# 05_Connector.net
KiCad netlist of a schematic drawn in Altium Designer
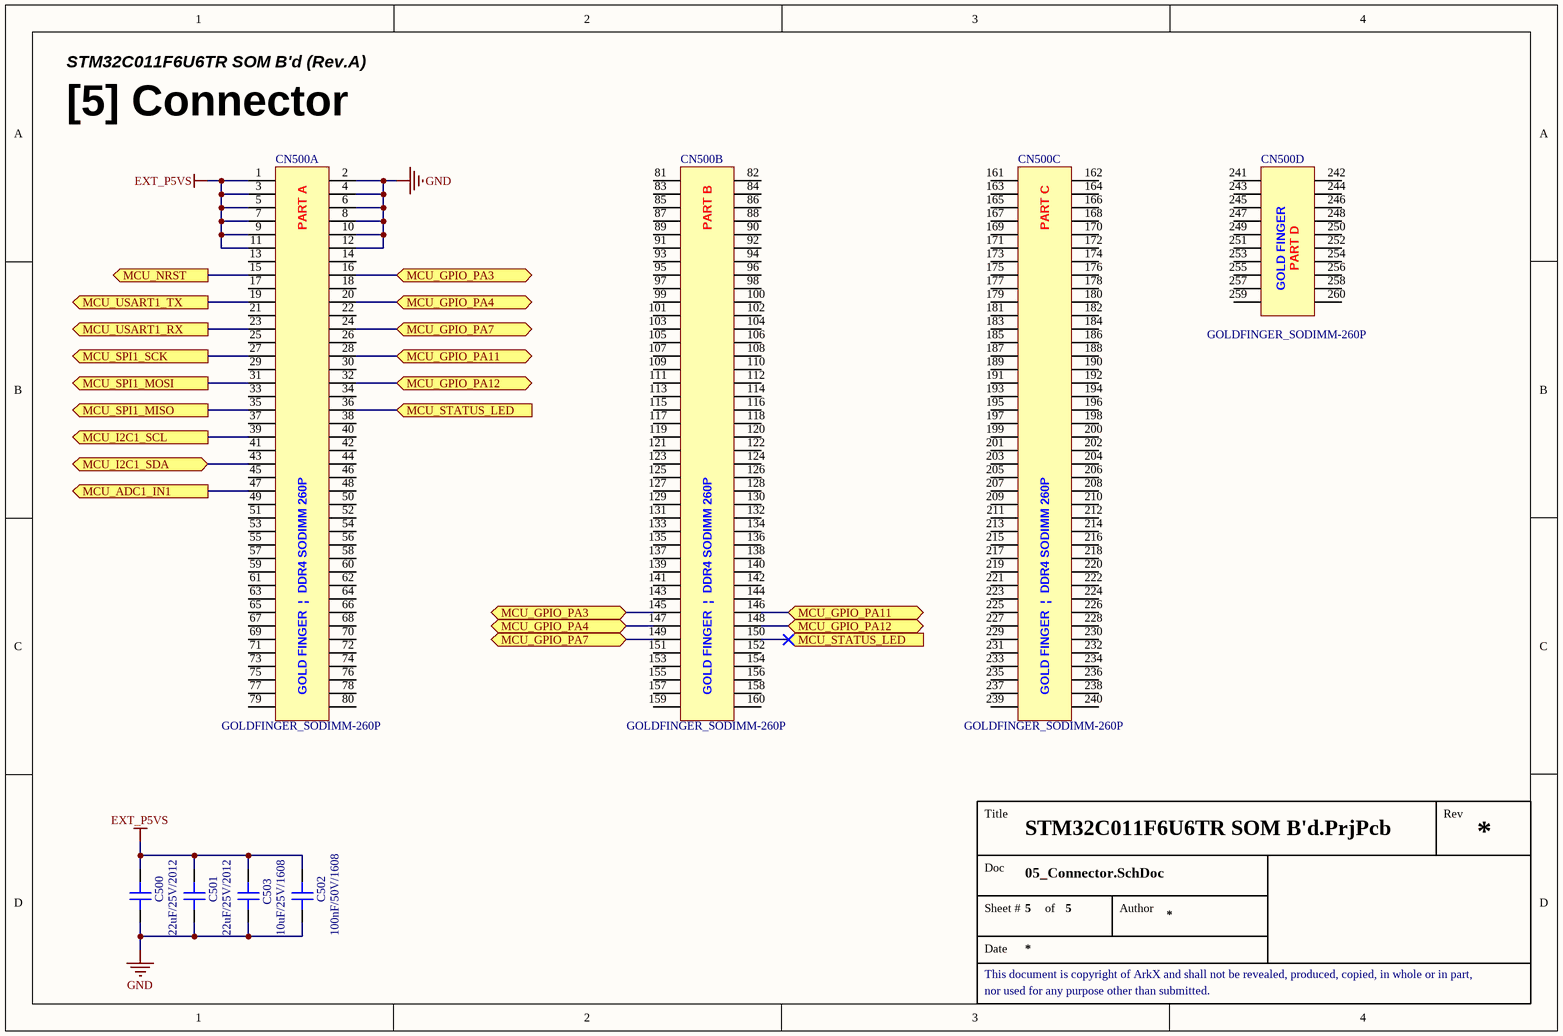
[diagram p0: 05_Connector.SchDoc]

(export (version "E")
  (design (tool "Eeschema 10.0.6"))
  (components
    (comp (ref "C500")
      (value "22uF/25V/2012")
      (footprint "CAP 2012 (0805_INCH)")
      (description "Ceramic CAP_22uF/25V/2012")
      (fields (field (name "LCSC PART #") "C45783"))
      (libsource (lib "Arkx") (part "CAP_22uF/25V/2012"))
    )
    (comp (ref "C501")
      (value "22uF/25V/2012")
      (footprint "CAP 2012 (0805_INCH)")
      (description "Ceramic CAP_22uF/25V/2012")
      (fields (field (name "LCSC PART #") "C45783"))
      (libsource (lib "Arkx") (part "CAP_22uF/25V/2012"))
    )
    (comp (ref "C502")
      (value "100nF/50V/1608")
      (footprint "CAP 1608 (0603_INCH)")
      (description "Ceramic CAP_100nF/50V/1608")
      (fields (field (name "LCSC PART #") "C14663"))
      (libsource (lib "Arkx") (part "CAP_100nF/50V/1608"))
    )
    (comp (ref "C503")
      (value "10uF/25V/1608")
      (footprint "CAP 1608 (0603_INCH)")
      (description "Ceramic CAP_10uF/25V/1608")
      (fields (field (name "LCSC PART #") "C96446"))
      (libsource (lib "Arkx") (part "CAP_10uF/25V/1608"))
    )
    (comp (ref "CN500")
      (value "GOLDFINGER_SODIMM-260P")
      (footprint "CON_DDR4-SODIMM-260P_EDGE-CONNECTOR")
      (description "GOLD-FINGER_DDR4-SODIMM-260P")
      (fields (field (name "MATING PART NUMBER") "2309409-1"))
      (libsource (lib "Arkx") (part "CON_GOLD-FINGER_DDR4-SODIMM-260P"))
    )
  )
  (nets
    (net (code "1") (name "/MCU_ADC1_IN1") (class "Default")
      (node (ref "CN500") (pin "47") (pinfunction "47_47") (pintype "passive"))
    )
    (net (code "2") (name "/MCU_GPIO_PA3") (class "Default")
      (node (ref "CN500") (pin "145") (pinfunction "145_145") (pintype "passive"))
      (node (ref "CN500") (pin "16") (pinfunction "16_16") (pintype "passive"))
    )
    (net (code "3") (name "/MCU_GPIO_PA4") (class "Default")
      (node (ref "CN500") (pin "147") (pinfunction "147_147") (pintype "passive"))
      (node (ref "CN500") (pin "20") (pinfunction "20_20") (pintype "passive"))
    )
    (net (code "4") (name "/MCU_GPIO_PA7") (class "Default")
      (node (ref "CN500") (pin "149") (pinfunction "149_149") (pintype "passive"))
      (node (ref "CN500") (pin "24") (pinfunction "24_24") (pintype "passive"))
    )
    (net (code "5") (name "/MCU_GPIO_PA11") (class "Default")
      (node (ref "CN500") (pin "146") (pinfunction "146_146") (pintype "passive"))
      (node (ref "CN500") (pin "28") (pinfunction "28_28") (pintype "passive"))
    )
    (net (code "6") (name "/MCU_GPIO_PA12") (class "Default")
      (node (ref "CN500") (pin "148") (pinfunction "148_148") (pintype "passive"))
      (node (ref "CN500") (pin "32") (pinfunction "32_32") (pintype "passive"))
    )
    (net (code "7") (name "/MCU_I2C1_SCL") (class "Default")
      (node (ref "CN500") (pin "39") (pinfunction "39_39") (pintype "passive"))
    )
    (net (code "8") (name "/MCU_I2C1_SDA") (class "Default")
      (node (ref "CN500") (pin "43") (pinfunction "43_43") (pintype "passive"))
    )
    (net (code "9") (name "/MCU_NRST") (class "Default")
      (node (ref "CN500") (pin "15") (pinfunction "15_15") (pintype "passive"))
    )
    (net (code "10") (name "/MCU_SPI1_MISO") (class "Default")
      (node (ref "CN500") (pin "35") (pinfunction "35_35") (pintype "passive"))
    )
    (net (code "11") (name "/MCU_SPI1_MOSI") (class "Default")
      (node (ref "CN500") (pin "31") (pinfunction "31_31") (pintype "passive"))
    )
    (net (code "12") (name "/MCU_SPI1_SCK") (class "Default")
      (node (ref "CN500") (pin "27") (pinfunction "27_27") (pintype "passive"))
    )
    (net (code "13") (name "/MCU_STATUS_LED") (class "Default")
      (node (ref "CN500") (pin "150") (pinfunction "150_150") (pintype "passive"))
      (node (ref "CN500") (pin "36") (pinfunction "36_36") (pintype "passive"))
    )
    (net (code "14") (name "/MCU_USART1_RX") (class "Default")
      (node (ref "CN500") (pin "23") (pinfunction "23_23") (pintype "passive"))
    )
    (net (code "15") (name "/MCU_USART1_TX") (class "Default")
      (node (ref "CN500") (pin "19") (pinfunction "19_19") (pintype "passive"))
    )
    (net (code "16") (name "EXT_P5VS") (class "Default")
      (node (ref "C500") (pin "2") (pinfunction "2_2") (pintype "passive"))
      (node (ref "C501") (pin "2") (pinfunction "2_2") (pintype "passive"))
      (node (ref "C502") (pin "2") (pinfunction "2_2") (pintype "passive"))
      (node (ref "C503") (pin "2") (pinfunction "2_2") (pintype "passive"))
      (node (ref "CN500") (pin "1") (pinfunction "1_1") (pintype "passive"))
      (node (ref "CN500") (pin "11") (pinfunction "11_11") (pintype "passive"))
      (node (ref "CN500") (pin "3") (pinfunction "3_3") (pintype "passive"))
      (node (ref "CN500") (pin "5") (pinfunction "5_5") (pintype "passive"))
      (node (ref "CN500") (pin "7") (pinfunction "7_7") (pintype "passive"))
      (node (ref "CN500") (pin "9") (pinfunction "9_9") (pintype "passive"))
    )
    (net (code "17") (name "GND") (class "Default")
      (node (ref "C500") (pin "1") (pinfunction "1_1") (pintype "passive"))
      (node (ref "C501") (pin "1") (pinfunction "1_1") (pintype "passive"))
      (node (ref "C502") (pin "1") (pinfunction "1_1") (pintype "passive"))
      (node (ref "C503") (pin "1") (pinfunction "1_1") (pintype "passive"))
      (node (ref "CN500") (pin "10") (pinfunction "10_10") (pintype "passive"))
      (node (ref "CN500") (pin "12") (pinfunction "12_12") (pintype "passive"))
      (node (ref "CN500") (pin "2") (pinfunction "2_2") (pintype "passive"))
      (node (ref "CN500") (pin "4") (pinfunction "4_4") (pintype "passive"))
      (node (ref "CN500") (pin "6") (pinfunction "6_6") (pintype "passive"))
      (node (ref "CN500") (pin "8") (pinfunction "8_8") (pintype "passive"))
    )
    (net (code "18") (name "unconnected-(CN500-Pad13)") (class "Default")
      (node (ref "CN500") (pin "13") (pinfunction "13_13") (pintype "passive"))
    )
    (net (code "19") (name "unconnected-(CN500-Pad14)") (class "Default")
      (node (ref "CN500") (pin "14") (pinfunction "14_14") (pintype "passive"))
    )
    (net (code "20") (name "unconnected-(CN500-Pad17)") (class "Default")
      (node (ref "CN500") (pin "17") (pinfunction "17_17") (pintype "passive"))
    )
    (net (code "21") (name "unconnected-(CN500-Pad18)") (class "Default")
      (node (ref "CN500") (pin "18") (pinfunction "18_18") (pintype "passive"))
    )
    (net (code "22") (name "unconnected-(CN500-Pad21)") (class "Default")
      (node (ref "CN500") (pin "21") (pinfunction "21_21") (pintype "passive"))
    )
    (net (code "23") (name "unconnected-(CN500-Pad22)") (class "Default")
      (node (ref "CN500") (pin "22") (pinfunction "22_22") (pintype "passive"))
    )
    (net (code "24") (name "unconnected-(CN500-Pad25)") (class "Default")
      (node (ref "CN500") (pin "25") (pinfunction "25_25") (pintype "passive"))
    )
    (net (code "25") (name "unconnected-(CN500-Pad26)") (class "Default")
      (node (ref "CN500") (pin "26") (pinfunction "26_26") (pintype "passive"))
    )
    (net (code "26") (name "unconnected-(CN500-Pad29)") (class "Default")
      (node (ref "CN500") (pin "29") (pinfunction "29_29") (pintype "passive"))
    )
    (net (code "27") (name "unconnected-(CN500-Pad30)") (class "Default")
      (node (ref "CN500") (pin "30") (pinfunction "30_30") (pintype "passive"))
    )
    (net (code "28") (name "unconnected-(CN500-Pad33)") (class "Default")
      (node (ref "CN500") (pin "33") (pinfunction "33_33") (pintype "passive"))
    )
    (net (code "29") (name "unconnected-(CN500-Pad34)") (class "Default")
      (node (ref "CN500") (pin "34") (pinfunction "34_34") (pintype "passive"))
    )
    (net (code "30") (name "unconnected-(CN500-Pad37)") (class "Default")
      (node (ref "CN500") (pin "37") (pinfunction "37_37") (pintype "passive"))
    )
    (net (code "31") (name "unconnected-(CN500-Pad38)") (class "Default")
      (node (ref "CN500") (pin "38") (pinfunction "38_38") (pintype "passive"))
    )
    (net (code "32") (name "unconnected-(CN500-Pad40)") (class "Default")
      (node (ref "CN500") (pin "40") (pinfunction "40_40") (pintype "passive"))
    )
    (net (code "33") (name "unconnected-(CN500-Pad41)") (class "Default")
      (node (ref "CN500") (pin "41") (pinfunction "41_41") (pintype "passive"))
    )
    (net (code "34") (name "unconnected-(CN500-Pad42)") (class "Default")
      (node (ref "CN500") (pin "42") (pinfunction "42_42") (pintype "passive"))
    )
    (net (code "35") (name "unconnected-(CN500-Pad44)") (class "Default")
      (node (ref "CN500") (pin "44") (pinfunction "44_44") (pintype "passive"))
    )
    (net (code "36") (name "unconnected-(CN500-Pad45)") (class "Default")
      (node (ref "CN500") (pin "45") (pinfunction "45_45") (pintype "passive"))
    )
    (net (code "37") (name "unconnected-(CN500-Pad46)") (class "Default")
      (node (ref "CN500") (pin "46") (pinfunction "46_46") (pintype "passive"))
    )
    (net (code "38") (name "unconnected-(CN500-Pad48)") (class "Default")
      (node (ref "CN500") (pin "48") (pinfunction "48_48") (pintype "passive"))
    )
    (net (code "39") (name "unconnected-(CN500-Pad49)") (class "Default")
      (node (ref "CN500") (pin "49") (pinfunction "49_49") (pintype "passive"))
    )
    (net (code "40") (name "unconnected-(CN500-Pad50)") (class "Default")
      (node (ref "CN500") (pin "50") (pinfunction "50_50") (pintype "passive"))
    )
    (net (code "41") (name "unconnected-(CN500-Pad51)") (class "Default")
      (node (ref "CN500") (pin "51") (pinfunction "51_51") (pintype "passive"))
    )
    (net (code "42") (name "unconnected-(CN500-Pad52)") (class "Default")
      (node (ref "CN500") (pin "52") (pinfunction "52_52") (pintype "passive"))
    )
    (net (code "43") (name "unconnected-(CN500-Pad53)") (class "Default")
      (node (ref "CN500") (pin "53") (pinfunction "53_53") (pintype "passive"))
    )
    (net (code "44") (name "unconnected-(CN500-Pad54)") (class "Default")
      (node (ref "CN500") (pin "54") (pinfunction "54_54") (pintype "passive"))
    )
    (net (code "45") (name "unconnected-(CN500-Pad55)") (class "Default")
      (node (ref "CN500") (pin "55") (pinfunction "55_55") (pintype "passive"))
    )
    (net (code "46") (name "unconnected-(CN500-Pad56)") (class "Default")
      (node (ref "CN500") (pin "56") (pinfunction "56_56") (pintype "passive"))
    )
    (net (code "47") (name "unconnected-(CN500-Pad57)") (class "Default")
      (node (ref "CN500") (pin "57") (pinfunction "57_57") (pintype "passive"))
    )
    (net (code "48") (name "unconnected-(CN500-Pad58)") (class "Default")
      (node (ref "CN500") (pin "58") (pinfunction "58_58") (pintype "passive"))
    )
    (net (code "49") (name "unconnected-(CN500-Pad59)") (class "Default")
      (node (ref "CN500") (pin "59") (pinfunction "59_59") (pintype "passive"))
    )
    (net (code "50") (name "unconnected-(CN500-Pad60)") (class "Default")
      (node (ref "CN500") (pin "60") (pinfunction "60_60") (pintype "passive"))
    )
    (net (code "51") (name "unconnected-(CN500-Pad61)") (class "Default")
      (node (ref "CN500") (pin "61") (pinfunction "61_61") (pintype "passive"))
    )
    (net (code "52") (name "unconnected-(CN500-Pad62)") (class "Default")
      (node (ref "CN500") (pin "62") (pinfunction "62_62") (pintype "passive"))
    )
    (net (code "53") (name "unconnected-(CN500-Pad63)") (class "Default")
      (node (ref "CN500") (pin "63") (pinfunction "63_63") (pintype "passive"))
    )
    (net (code "54") (name "unconnected-(CN500-Pad64)") (class "Default")
      (node (ref "CN500") (pin "64") (pinfunction "64_64") (pintype "passive"))
    )
    (net (code "55") (name "unconnected-(CN500-Pad65)") (class "Default")
      (node (ref "CN500") (pin "65") (pinfunction "65_65") (pintype "passive"))
    )
    (net (code "56") (name "unconnected-(CN500-Pad66)") (class "Default")
      (node (ref "CN500") (pin "66") (pinfunction "66_66") (pintype "passive"))
    )
    (net (code "57") (name "unconnected-(CN500-Pad67)") (class "Default")
      (node (ref "CN500") (pin "67") (pinfunction "67_67") (pintype "passive"))
    )
    (net (code "58") (name "unconnected-(CN500-Pad68)") (class "Default")
      (node (ref "CN500") (pin "68") (pinfunction "68_68") (pintype "passive"))
    )
    (net (code "59") (name "unconnected-(CN500-Pad69)") (class "Default")
      (node (ref "CN500") (pin "69") (pinfunction "69_69") (pintype "passive"))
    )
    (net (code "60") (name "unconnected-(CN500-Pad70)") (class "Default")
      (node (ref "CN500") (pin "70") (pinfunction "70_70") (pintype "passive"))
    )
    (net (code "61") (name "unconnected-(CN500-Pad71)") (class "Default")
      (node (ref "CN500") (pin "71") (pinfunction "71_71") (pintype "passive"))
    )
    (net (code "62") (name "unconnected-(CN500-Pad72)") (class "Default")
      (node (ref "CN500") (pin "72") (pinfunction "72_72") (pintype "passive"))
    )
    (net (code "63") (name "unconnected-(CN500-Pad73)") (class "Default")
      (node (ref "CN500") (pin "73") (pinfunction "73_73") (pintype "passive"))
    )
    (net (code "64") (name "unconnected-(CN500-Pad74)") (class "Default")
      (node (ref "CN500") (pin "74") (pinfunction "74_74") (pintype "passive"))
    )
    (net (code "65") (name "unconnected-(CN500-Pad75)") (class "Default")
      (node (ref "CN500") (pin "75") (pinfunction "75_75") (pintype "passive"))
    )
    (net (code "66") (name "unconnected-(CN500-Pad76)") (class "Default")
      (node (ref "CN500") (pin "76") (pinfunction "76_76") (pintype "passive"))
    )
    (net (code "67") (name "unconnected-(CN500-Pad77)") (class "Default")
      (node (ref "CN500") (pin "77") (pinfunction "77_77") (pintype "passive"))
    )
    (net (code "68") (name "unconnected-(CN500-Pad78)") (class "Default")
      (node (ref "CN500") (pin "78") (pinfunction "78_78") (pintype "passive"))
    )
    (net (code "69") (name "unconnected-(CN500-Pad79)") (class "Default")
      (node (ref "CN500") (pin "79") (pinfunction "79_79") (pintype "passive"))
    )
    (net (code "70") (name "unconnected-(CN500-Pad80)") (class "Default")
      (node (ref "CN500") (pin "80") (pinfunction "80_80") (pintype "passive"))
    )
    (net (code "71") (name "unconnected-(CN500-Pad81)") (class "Default")
      (node (ref "CN500") (pin "81") (pinfunction "81_81") (pintype "passive"))
    )
    (net (code "72") (name "unconnected-(CN500-Pad82)") (class "Default")
      (node (ref "CN500") (pin "82") (pinfunction "82_82") (pintype "passive"))
    )
    (net (code "73") (name "unconnected-(CN500-Pad83)") (class "Default")
      (node (ref "CN500") (pin "83") (pinfunction "83_83") (pintype "passive"))
    )
    (net (code "74") (name "unconnected-(CN500-Pad84)") (class "Default")
      (node (ref "CN500") (pin "84") (pinfunction "84_84") (pintype "passive"))
    )
    (net (code "75") (name "unconnected-(CN500-Pad85)") (class "Default")
      (node (ref "CN500") (pin "85") (pinfunction "85_85") (pintype "passive"))
    )
    (net (code "76") (name "unconnected-(CN500-Pad86)") (class "Default")
      (node (ref "CN500") (pin "86") (pinfunction "86_86") (pintype "passive"))
    )
    (net (code "77") (name "unconnected-(CN500-Pad87)") (class "Default")
      (node (ref "CN500") (pin "87") (pinfunction "87_87") (pintype "passive"))
    )
    (net (code "78") (name "unconnected-(CN500-Pad88)") (class "Default")
      (node (ref "CN500") (pin "88") (pinfunction "88_88") (pintype "passive"))
    )
    (net (code "79") (name "unconnected-(CN500-Pad89)") (class "Default")
      (node (ref "CN500") (pin "89") (pinfunction "89_89") (pintype "passive"))
    )
    (net (code "80") (name "unconnected-(CN500-Pad90)") (class "Default")
      (node (ref "CN500") (pin "90") (pinfunction "90_90") (pintype "passive"))
    )
    (net (code "81") (name "unconnected-(CN500-Pad91)") (class "Default")
      (node (ref "CN500") (pin "91") (pinfunction "91_91") (pintype "passive"))
    )
    (net (code "82") (name "unconnected-(CN500-Pad92)") (class "Default")
      (node (ref "CN500") (pin "92") (pinfunction "92_92") (pintype "passive"))
    )
    (net (code "83") (name "unconnected-(CN500-Pad93)") (class "Default")
      (node (ref "CN500") (pin "93") (pinfunction "93_93") (pintype "passive"))
    )
    (net (code "84") (name "unconnected-(CN500-Pad94)") (class "Default")
      (node (ref "CN500") (pin "94") (pinfunction "94_94") (pintype "passive"))
    )
    (net (code "85") (name "unconnected-(CN500-Pad95)") (class "Default")
      (node (ref "CN500") (pin "95") (pinfunction "95_95") (pintype "passive"))
    )
    (net (code "86") (name "unconnected-(CN500-Pad96)") (class "Default")
      (node (ref "CN500") (pin "96") (pinfunction "96_96") (pintype "passive"))
    )
    (net (code "87") (name "unconnected-(CN500-Pad97)") (class "Default")
      (node (ref "CN500") (pin "97") (pinfunction "97_97") (pintype "passive"))
    )
    (net (code "88") (name "unconnected-(CN500-Pad98)") (class "Default")
      (node (ref "CN500") (pin "98") (pinfunction "98_98") (pintype "passive"))
    )
    (net (code "89") (name "unconnected-(CN500-Pad99)") (class "Default")
      (node (ref "CN500") (pin "99") (pinfunction "99_99") (pintype "passive"))
    )
    (net (code "90") (name "unconnected-(CN500-Pad100)") (class "Default")
      (node (ref "CN500") (pin "100") (pinfunction "100_100") (pintype "passive"))
    )
    (net (code "91") (name "unconnected-(CN500-Pad101)") (class "Default")
      (node (ref "CN500") (pin "101") (pinfunction "101_101") (pintype "passive"))
    )
    (net (code "92") (name "unconnected-(CN500-Pad102)") (class "Default")
      (node (ref "CN500") (pin "102") (pinfunction "102_102") (pintype "passive"))
    )
    (net (code "93") (name "unconnected-(CN500-Pad103)") (class "Default")
      (node (ref "CN500") (pin "103") (pinfunction "103_103") (pintype "passive"))
    )
    (net (code "94") (name "unconnected-(CN500-Pad104)") (class "Default")
      (node (ref "CN500") (pin "104") (pinfunction "104_104") (pintype "passive"))
    )
    (net (code "95") (name "unconnected-(CN500-Pad105)") (class "Default")
      (node (ref "CN500") (pin "105") (pinfunction "105_105") (pintype "passive"))
    )
    (net (code "96") (name "unconnected-(CN500-Pad106)") (class "Default")
      (node (ref "CN500") (pin "106") (pinfunction "106_106") (pintype "passive"))
    )
    (net (code "97") (name "unconnected-(CN500-Pad107)") (class "Default")
      (node (ref "CN500") (pin "107") (pinfunction "107_107") (pintype "passive"))
    )
    (net (code "98") (name "unconnected-(CN500-Pad108)") (class "Default")
      (node (ref "CN500") (pin "108") (pinfunction "108_108") (pintype "passive"))
    )
    (net (code "99") (name "unconnected-(CN500-Pad109)") (class "Default")
      (node (ref "CN500") (pin "109") (pinfunction "109_109") (pintype "passive"))
    )
    (net (code "100") (name "unconnected-(CN500-Pad110)") (class "Default")
      (node (ref "CN500") (pin "110") (pinfunction "110_110") (pintype "passive"))
    )
    (net (code "101") (name "unconnected-(CN500-Pad111)") (class "Default")
      (node (ref "CN500") (pin "111") (pinfunction "111_111") (pintype "passive"))
    )
    (net (code "102") (name "unconnected-(CN500-Pad112)") (class "Default")
      (node (ref "CN500") (pin "112") (pinfunction "112_112") (pintype "passive"))
    )
    (net (code "103") (name "unconnected-(CN500-Pad113)") (class "Default")
      (node (ref "CN500") (pin "113") (pinfunction "113_113") (pintype "passive"))
    )
    (net (code "104") (name "unconnected-(CN500-Pad114)") (class "Default")
      (node (ref "CN500") (pin "114") (pinfunction "114_114") (pintype "passive"))
    )
    (net (code "105") (name "unconnected-(CN500-Pad115)") (class "Default")
      (node (ref "CN500") (pin "115") (pinfunction "115_115") (pintype "passive"))
    )
    (net (code "106") (name "unconnected-(CN500-Pad116)") (class "Default")
      (node (ref "CN500") (pin "116") (pinfunction "116_116") (pintype "passive"))
    )
    (net (code "107") (name "unconnected-(CN500-Pad117)") (class "Default")
      (node (ref "CN500") (pin "117") (pinfunction "117_117") (pintype "passive"))
    )
    (net (code "108") (name "unconnected-(CN500-Pad118)") (class "Default")
      (node (ref "CN500") (pin "118") (pinfunction "118_118") (pintype "passive"))
    )
    (net (code "109") (name "unconnected-(CN500-Pad119)") (class "Default")
      (node (ref "CN500") (pin "119") (pinfunction "119_119") (pintype "passive"))
    )
    (net (code "110") (name "unconnected-(CN500-Pad120)") (class "Default")
      (node (ref "CN500") (pin "120") (pinfunction "120_120") (pintype "passive"))
    )
    (net (code "111") (name "unconnected-(CN500-Pad121)") (class "Default")
      (node (ref "CN500") (pin "121") (pinfunction "121_121") (pintype "passive"))
    )
    (net (code "112") (name "unconnected-(CN500-Pad122)") (class "Default")
      (node (ref "CN500") (pin "122") (pinfunction "122_122") (pintype "passive"))
    )
    (net (code "113") (name "unconnected-(CN500-Pad123)") (class "Default")
      (node (ref "CN500") (pin "123") (pinfunction "123_123") (pintype "passive"))
    )
    (net (code "114") (name "unconnected-(CN500-Pad124)") (class "Default")
      (node (ref "CN500") (pin "124") (pinfunction "124_124") (pintype "passive"))
    )
    (net (code "115") (name "unconnected-(CN500-Pad125)") (class "Default")
      (node (ref "CN500") (pin "125") (pinfunction "125_125") (pintype "passive"))
    )
    (net (code "116") (name "unconnected-(CN500-Pad126)") (class "Default")
      (node (ref "CN500") (pin "126") (pinfunction "126_126") (pintype "passive"))
    )
    (net (code "117") (name "unconnected-(CN500-Pad127)") (class "Default")
      (node (ref "CN500") (pin "127") (pinfunction "127_127") (pintype "passive"))
    )
    (net (code "118") (name "unconnected-(CN500-Pad128)") (class "Default")
      (node (ref "CN500") (pin "128") (pinfunction "128_128") (pintype "passive"))
    )
    (net (code "119") (name "unconnected-(CN500-Pad129)") (class "Default")
      (node (ref "CN500") (pin "129") (pinfunction "129_129") (pintype "passive"))
    )
    (net (code "120") (name "unconnected-(CN500-Pad130)") (class "Default")
      (node (ref "CN500") (pin "130") (pinfunction "130_130") (pintype "passive"))
    )
    (net (code "121") (name "unconnected-(CN500-Pad131)") (class "Default")
      (node (ref "CN500") (pin "131") (pinfunction "131_131") (pintype "passive"))
    )
    (net (code "122") (name "unconnected-(CN500-Pad132)") (class "Default")
      (node (ref "CN500") (pin "132") (pinfunction "132_132") (pintype "passive"))
    )
    (net (code "123") (name "unconnected-(CN500-Pad133)") (class "Default")
      (node (ref "CN500") (pin "133") (pinfunction "133_133") (pintype "passive"))
    )
    (net (code "124") (name "unconnected-(CN500-Pad134)") (class "Default")
      (node (ref "CN500") (pin "134") (pinfunction "134_134") (pintype "passive"))
    )
    (net (code "125") (name "unconnected-(CN500-Pad135)") (class "Default")
      (node (ref "CN500") (pin "135") (pinfunction "135_135") (pintype "passive"))
    )
    (net (code "126") (name "unconnected-(CN500-Pad136)") (class "Default")
      (node (ref "CN500") (pin "136") (pinfunction "136_136") (pintype "passive"))
    )
    (net (code "127") (name "unconnected-(CN500-Pad137)") (class "Default")
      (node (ref "CN500") (pin "137") (pinfunction "137_137") (pintype "passive"))
    )
    (net (code "128") (name "unconnected-(CN500-Pad138)") (class "Default")
      (node (ref "CN500") (pin "138") (pinfunction "138_138") (pintype "passive"))
    )
    (net (code "129") (name "unconnected-(CN500-Pad139)") (class "Default")
      (node (ref "CN500") (pin "139") (pinfunction "139_139") (pintype "passive"))
    )
    (net (code "130") (name "unconnected-(CN500-Pad140)") (class "Default")
      (node (ref "CN500") (pin "140") (pinfunction "140_140") (pintype "passive"))
    )
    (net (code "131") (name "unconnected-(CN500-Pad141)") (class "Default")
      (node (ref "CN500") (pin "141") (pinfunction "141_141") (pintype "passive"))
    )
    (net (code "132") (name "unconnected-(CN500-Pad142)") (class "Default")
      (node (ref "CN500") (pin "142") (pinfunction "142_142") (pintype "passive"))
    )
    (net (code "133") (name "unconnected-(CN500-Pad143)") (class "Default")
      (node (ref "CN500") (pin "143") (pinfunction "143_143") (pintype "passive"))
    )
    (net (code "134") (name "unconnected-(CN500-Pad144)") (class "Default")
      (node (ref "CN500") (pin "144") (pinfunction "144_144") (pintype "passive"))
    )
    (net (code "135") (name "unconnected-(CN500-Pad151)") (class "Default")
      (node (ref "CN500") (pin "151") (pinfunction "151_151") (pintype "passive"))
    )
    (net (code "136") (name "unconnected-(CN500-Pad152)") (class "Default")
      (node (ref "CN500") (pin "152") (pinfunction "152_152") (pintype "passive"))
    )
    (net (code "137") (name "unconnected-(CN500-Pad153)") (class "Default")
      (node (ref "CN500") (pin "153") (pinfunction "153_153") (pintype "passive"))
    )
    (net (code "138") (name "unconnected-(CN500-Pad154)") (class "Default")
      (node (ref "CN500") (pin "154") (pinfunction "154_154") (pintype "passive"))
    )
    (net (code "139") (name "unconnected-(CN500-Pad155)") (class "Default")
      (node (ref "CN500") (pin "155") (pinfunction "155_155") (pintype "passive"))
    )
    (net (code "140") (name "unconnected-(CN500-Pad156)") (class "Default")
      (node (ref "CN500") (pin "156") (pinfunction "156_156") (pintype "passive"))
    )
    (net (code "141") (name "unconnected-(CN500-Pad157)") (class "Default")
      (node (ref "CN500") (pin "157") (pinfunction "157_157") (pintype "passive"))
    )
    (net (code "142") (name "unconnected-(CN500-Pad158)") (class "Default")
      (node (ref "CN500") (pin "158") (pinfunction "158_158") (pintype "passive"))
    )
    (net (code "143") (name "unconnected-(CN500-Pad159)") (class "Default")
      (node (ref "CN500") (pin "159") (pinfunction "159_159") (pintype "passive"))
    )
    (net (code "144") (name "unconnected-(CN500-Pad160)") (class "Default")
      (node (ref "CN500") (pin "160") (pinfunction "160_160") (pintype "passive"))
    )
    (net (code "145") (name "unconnected-(CN500-Pad161)") (class "Default")
      (node (ref "CN500") (pin "161") (pinfunction "161_161") (pintype "passive"))
    )
    (net (code "146") (name "unconnected-(CN500-Pad162)") (class "Default")
      (node (ref "CN500") (pin "162") (pinfunction "162_162") (pintype "passive"))
    )
    (net (code "147") (name "unconnected-(CN500-Pad163)") (class "Default")
      (node (ref "CN500") (pin "163") (pinfunction "163_163") (pintype "passive"))
    )
    (net (code "148") (name "unconnected-(CN500-Pad164)") (class "Default")
      (node (ref "CN500") (pin "164") (pinfunction "164_164") (pintype "passive"))
    )
    (net (code "149") (name "unconnected-(CN500-Pad165)") (class "Default")
      (node (ref "CN500") (pin "165") (pinfunction "165_165") (pintype "passive"))
    )
    (net (code "150") (name "unconnected-(CN500-Pad166)") (class "Default")
      (node (ref "CN500") (pin "166") (pinfunction "166_166") (pintype "passive"))
    )
    (net (code "151") (name "unconnected-(CN500-Pad167)") (class "Default")
      (node (ref "CN500") (pin "167") (pinfunction "167_167") (pintype "passive"))
    )
    (net (code "152") (name "unconnected-(CN500-Pad168)") (class "Default")
      (node (ref "CN500") (pin "168") (pinfunction "168_168") (pintype "passive"))
    )
    (net (code "153") (name "unconnected-(CN500-Pad169)") (class "Default")
      (node (ref "CN500") (pin "169") (pinfunction "169_169") (pintype "passive"))
    )
    (net (code "154") (name "unconnected-(CN500-Pad170)") (class "Default")
      (node (ref "CN500") (pin "170") (pinfunction "170_170") (pintype "passive"))
    )
    (net (code "155") (name "unconnected-(CN500-Pad171)") (class "Default")
      (node (ref "CN500") (pin "171") (pinfunction "171_171") (pintype "passive"))
    )
    (net (code "156") (name "unconnected-(CN500-Pad172)") (class "Default")
      (node (ref "CN500") (pin "172") (pinfunction "172_172") (pintype "passive"))
    )
    (net (code "157") (name "unconnected-(CN500-Pad173)") (class "Default")
      (node (ref "CN500") (pin "173") (pinfunction "173_173") (pintype "passive"))
    )
    (net (code "158") (name "unconnected-(CN500-Pad174)") (class "Default")
      (node (ref "CN500") (pin "174") (pinfunction "174_174") (pintype "passive"))
    )
    (net (code "159") (name "unconnected-(CN500-Pad175)") (class "Default")
      (node (ref "CN500") (pin "175") (pinfunction "175_175") (pintype "passive"))
    )
    (net (code "160") (name "unconnected-(CN500-Pad176)") (class "Default")
      (node (ref "CN500") (pin "176") (pinfunction "176_176") (pintype "passive"))
    )
    (net (code "161") (name "unconnected-(CN500-Pad177)") (class "Default")
      (node (ref "CN500") (pin "177") (pinfunction "177_177") (pintype "passive"))
    )
    (net (code "162") (name "unconnected-(CN500-Pad178)") (class "Default")
      (node (ref "CN500") (pin "178") (pinfunction "178_178") (pintype "passive"))
    )
    (net (code "163") (name "unconnected-(CN500-Pad179)") (class "Default")
      (node (ref "CN500") (pin "179") (pinfunction "179_179") (pintype "passive"))
    )
    (net (code "164") (name "unconnected-(CN500-Pad180)") (class "Default")
      (node (ref "CN500") (pin "180") (pinfunction "180_180") (pintype "passive"))
    )
    (net (code "165") (name "unconnected-(CN500-Pad181)") (class "Default")
      (node (ref "CN500") (pin "181") (pinfunction "181_181") (pintype "passive"))
    )
    (net (code "166") (name "unconnected-(CN500-Pad182)") (class "Default")
      (node (ref "CN500") (pin "182") (pinfunction "182_182") (pintype "passive"))
    )
    (net (code "167") (name "unconnected-(CN500-Pad183)") (class "Default")
      (node (ref "CN500") (pin "183") (pinfunction "183_183") (pintype "passive"))
    )
    (net (code "168") (name "unconnected-(CN500-Pad184)") (class "Default")
      (node (ref "CN500") (pin "184") (pinfunction "184_184") (pintype "passive"))
    )
    (net (code "169") (name "unconnected-(CN500-Pad185)") (class "Default")
      (node (ref "CN500") (pin "185") (pinfunction "185_185") (pintype "passive"))
    )
    (net (code "170") (name "unconnected-(CN500-Pad186)") (class "Default")
      (node (ref "CN500") (pin "186") (pinfunction "186_186") (pintype "passive"))
    )
    (net (code "171") (name "unconnected-(CN500-Pad187)") (class "Default")
      (node (ref "CN500") (pin "187") (pinfunction "187_187") (pintype "passive"))
    )
    (net (code "172") (name "unconnected-(CN500-Pad188)") (class "Default")
      (node (ref "CN500") (pin "188") (pinfunction "188_188") (pintype "passive"))
    )
    (net (code "173") (name "unconnected-(CN500-Pad189)") (class "Default")
      (node (ref "CN500") (pin "189") (pinfunction "189_189") (pintype "passive"))
    )
    (net (code "174") (name "unconnected-(CN500-Pad190)") (class "Default")
      (node (ref "CN500") (pin "190") (pinfunction "190_190") (pintype "passive"))
    )
    (net (code "175") (name "unconnected-(CN500-Pad191)") (class "Default")
      (node (ref "CN500") (pin "191") (pinfunction "191_191") (pintype "passive"))
    )
    (net (code "176") (name "unconnected-(CN500-Pad192)") (class "Default")
      (node (ref "CN500") (pin "192") (pinfunction "192_192") (pintype "passive"))
    )
    (net (code "177") (name "unconnected-(CN500-Pad193)") (class "Default")
      (node (ref "CN500") (pin "193") (pinfunction "193_193") (pintype "passive"))
    )
    (net (code "178") (name "unconnected-(CN500-Pad194)") (class "Default")
      (node (ref "CN500") (pin "194") (pinfunction "194_194") (pintype "passive"))
    )
    (net (code "179") (name "unconnected-(CN500-Pad195)") (class "Default")
      (node (ref "CN500") (pin "195") (pinfunction "195_195") (pintype "passive"))
    )
    (net (code "180") (name "unconnected-(CN500-Pad196)") (class "Default")
      (node (ref "CN500") (pin "196") (pinfunction "196_196") (pintype "passive"))
    )
    (net (code "181") (name "unconnected-(CN500-Pad197)") (class "Default")
      (node (ref "CN500") (pin "197") (pinfunction "197_197") (pintype "passive"))
    )
    (net (code "182") (name "unconnected-(CN500-Pad198)") (class "Default")
      (node (ref "CN500") (pin "198") (pinfunction "198_198") (pintype "passive"))
    )
    (net (code "183") (name "unconnected-(CN500-Pad199)") (class "Default")
      (node (ref "CN500") (pin "199") (pinfunction "199_199") (pintype "passive"))
    )
    (net (code "184") (name "unconnected-(CN500-Pad200)") (class "Default")
      (node (ref "CN500") (pin "200") (pinfunction "200_200") (pintype "passive"))
    )
    (net (code "185") (name "unconnected-(CN500-Pad201)") (class "Default")
      (node (ref "CN500") (pin "201") (pinfunction "201_201") (pintype "passive"))
    )
    (net (code "186") (name "unconnected-(CN500-Pad202)") (class "Default")
      (node (ref "CN500") (pin "202") (pinfunction "202_202") (pintype "passive"))
    )
    (net (code "187") (name "unconnected-(CN500-Pad203)") (class "Default")
      (node (ref "CN500") (pin "203") (pinfunction "203_203") (pintype "passive"))
    )
    (net (code "188") (name "unconnected-(CN500-Pad204)") (class "Default")
      (node (ref "CN500") (pin "204") (pinfunction "204_204") (pintype "passive"))
    )
    (net (code "189") (name "unconnected-(CN500-Pad205)") (class "Default")
      (node (ref "CN500") (pin "205") (pinfunction "205_205") (pintype "passive"))
    )
    (net (code "190") (name "unconnected-(CN500-Pad206)") (class "Default")
      (node (ref "CN500") (pin "206") (pinfunction "206_206") (pintype "passive"))
    )
    (net (code "191") (name "unconnected-(CN500-Pad207)") (class "Default")
      (node (ref "CN500") (pin "207") (pinfunction "207_207") (pintype "passive"))
    )
    (net (code "192") (name "unconnected-(CN500-Pad208)") (class "Default")
      (node (ref "CN500") (pin "208") (pinfunction "208_208") (pintype "passive"))
    )
    (net (code "193") (name "unconnected-(CN500-Pad209)") (class "Default")
      (node (ref "CN500") (pin "209") (pinfunction "209_209") (pintype "passive"))
    )
    (net (code "194") (name "unconnected-(CN500-Pad210)") (class "Default")
      (node (ref "CN500") (pin "210") (pinfunction "210_210") (pintype "passive"))
    )
    (net (code "195") (name "unconnected-(CN500-Pad211)") (class "Default")
      (node (ref "CN500") (pin "211") (pinfunction "211_211") (pintype "passive"))
    )
    (net (code "196") (name "unconnected-(CN500-Pad212)") (class "Default")
      (node (ref "CN500") (pin "212") (pinfunction "212_212") (pintype "passive"))
    )
    (net (code "197") (name "unconnected-(CN500-Pad213)") (class "Default")
      (node (ref "CN500") (pin "213") (pinfunction "213_213") (pintype "passive"))
    )
    (net (code "198") (name "unconnected-(CN500-Pad214)") (class "Default")
      (node (ref "CN500") (pin "214") (pinfunction "214_214") (pintype "passive"))
    )
    (net (code "199") (name "unconnected-(CN500-Pad215)") (class "Default")
      (node (ref "CN500") (pin "215") (pinfunction "215_215") (pintype "passive"))
    )
    (net (code "200") (name "unconnected-(CN500-Pad216)") (class "Default")
      (node (ref "CN500") (pin "216") (pinfunction "216_216") (pintype "passive"))
    )
    (net (code "201") (name "unconnected-(CN500-Pad217)") (class "Default")
      (node (ref "CN500") (pin "217") (pinfunction "217_217") (pintype "passive"))
    )
    (net (code "202") (name "unconnected-(CN500-Pad218)") (class "Default")
      (node (ref "CN500") (pin "218") (pinfunction "218_218") (pintype "passive"))
    )
    (net (code "203") (name "unconnected-(CN500-Pad219)") (class "Default")
      (node (ref "CN500") (pin "219") (pinfunction "219_219") (pintype "passive"))
    )
    (net (code "204") (name "unconnected-(CN500-Pad220)") (class "Default")
      (node (ref "CN500") (pin "220") (pinfunction "220_220") (pintype "passive"))
    )
    (net (code "205") (name "unconnected-(CN500-Pad221)") (class "Default")
      (node (ref "CN500") (pin "221") (pinfunction "221_221") (pintype "passive"))
    )
    (net (code "206") (name "unconnected-(CN500-Pad222)") (class "Default")
      (node (ref "CN500") (pin "222") (pinfunction "222_222") (pintype "passive"))
    )
    (net (code "207") (name "unconnected-(CN500-Pad223)") (class "Default")
      (node (ref "CN500") (pin "223") (pinfunction "223_223") (pintype "passive"))
    )
    (net (code "208") (name "unconnected-(CN500-Pad224)") (class "Default")
      (node (ref "CN500") (pin "224") (pinfunction "224_224") (pintype "passive"))
    )
    (net (code "209") (name "unconnected-(CN500-Pad225)") (class "Default")
      (node (ref "CN500") (pin "225") (pinfunction "225_225") (pintype "passive"))
    )
    (net (code "210") (name "unconnected-(CN500-Pad226)") (class "Default")
      (node (ref "CN500") (pin "226") (pinfunction "226_226") (pintype "passive"))
    )
    (net (code "211") (name "unconnected-(CN500-Pad227)") (class "Default")
      (node (ref "CN500") (pin "227") (pinfunction "227_227") (pintype "passive"))
    )
    (net (code "212") (name "unconnected-(CN500-Pad228)") (class "Default")
      (node (ref "CN500") (pin "228") (pinfunction "228_228") (pintype "passive"))
    )
    (net (code "213") (name "unconnected-(CN500-Pad229)") (class "Default")
      (node (ref "CN500") (pin "229") (pinfunction "229_229") (pintype "passive"))
    )
    (net (code "214") (name "unconnected-(CN500-Pad230)") (class "Default")
      (node (ref "CN500") (pin "230") (pinfunction "230_230") (pintype "passive"))
    )
    (net (code "215") (name "unconnected-(CN500-Pad231)") (class "Default")
      (node (ref "CN500") (pin "231") (pinfunction "231_231") (pintype "passive"))
    )
    (net (code "216") (name "unconnected-(CN500-Pad232)") (class "Default")
      (node (ref "CN500") (pin "232") (pinfunction "232_232") (pintype "passive"))
    )
    (net (code "217") (name "unconnected-(CN500-Pad233)") (class "Default")
      (node (ref "CN500") (pin "233") (pinfunction "233_233") (pintype "passive"))
    )
    (net (code "218") (name "unconnected-(CN500-Pad234)") (class "Default")
      (node (ref "CN500") (pin "234") (pinfunction "234_234") (pintype "passive"))
    )
    (net (code "219") (name "unconnected-(CN500-Pad235)") (class "Default")
      (node (ref "CN500") (pin "235") (pinfunction "235_235") (pintype "passive"))
    )
    (net (code "220") (name "unconnected-(CN500-Pad236)") (class "Default")
      (node (ref "CN500") (pin "236") (pinfunction "236_236") (pintype "passive"))
    )
    (net (code "221") (name "unconnected-(CN500-Pad237)") (class "Default")
      (node (ref "CN500") (pin "237") (pinfunction "237_237") (pintype "passive"))
    )
    (net (code "222") (name "unconnected-(CN500-Pad238)") (class "Default")
      (node (ref "CN500") (pin "238") (pinfunction "238_238") (pintype "passive"))
    )
    (net (code "223") (name "unconnected-(CN500-Pad239)") (class "Default")
      (node (ref "CN500") (pin "239") (pinfunction "239_239") (pintype "passive"))
    )
    (net (code "224") (name "unconnected-(CN500-Pad240)") (class "Default")
      (node (ref "CN500") (pin "240") (pinfunction "240_240") (pintype "passive"))
    )
    (net (code "225") (name "unconnected-(CN500-Pad241)") (class "Default")
      (node (ref "CN500") (pin "241") (pinfunction "241_241") (pintype "passive"))
    )
    (net (code "226") (name "unconnected-(CN500-Pad242)") (class "Default")
      (node (ref "CN500") (pin "242") (pinfunction "242_242") (pintype "passive"))
    )
    (net (code "227") (name "unconnected-(CN500-Pad243)") (class "Default")
      (node (ref "CN500") (pin "243") (pinfunction "243_243") (pintype "passive"))
    )
    (net (code "228") (name "unconnected-(CN500-Pad244)") (class "Default")
      (node (ref "CN500") (pin "244") (pinfunction "244_244") (pintype "passive"))
    )
    (net (code "229") (name "unconnected-(CN500-Pad245)") (class "Default")
      (node (ref "CN500") (pin "245") (pinfunction "245_245") (pintype "passive"))
    )
    (net (code "230") (name "unconnected-(CN500-Pad246)") (class "Default")
      (node (ref "CN500") (pin "246") (pinfunction "246_246") (pintype "passive"))
    )
    (net (code "231") (name "unconnected-(CN500-Pad247)") (class "Default")
      (node (ref "CN500") (pin "247") (pinfunction "247_247") (pintype "passive"))
    )
    (net (code "232") (name "unconnected-(CN500-Pad248)") (class "Default")
      (node (ref "CN500") (pin "248") (pinfunction "248_248") (pintype "passive"))
    )
    (net (code "233") (name "unconnected-(CN500-Pad249)") (class "Default")
      (node (ref "CN500") (pin "249") (pinfunction "249_249") (pintype "passive"))
    )
    (net (code "234") (name "unconnected-(CN500-Pad250)") (class "Default")
      (node (ref "CN500") (pin "250") (pinfunction "250_250") (pintype "passive"))
    )
    (net (code "235") (name "unconnected-(CN500-Pad251)") (class "Default")
      (node (ref "CN500") (pin "251") (pinfunction "251_251") (pintype "passive"))
    )
    (net (code "236") (name "unconnected-(CN500-Pad252)") (class "Default")
      (node (ref "CN500") (pin "252") (pinfunction "252_252") (pintype "passive"))
    )
    (net (code "237") (name "unconnected-(CN500-Pad253)") (class "Default")
      (node (ref "CN500") (pin "253") (pinfunction "253_253") (pintype "passive"))
    )
    (net (code "238") (name "unconnected-(CN500-Pad254)") (class "Default")
      (node (ref "CN500") (pin "254") (pinfunction "254_254") (pintype "passive"))
    )
    (net (code "239") (name "unconnected-(CN500-Pad255)") (class "Default")
      (node (ref "CN500") (pin "255") (pinfunction "255_255") (pintype "passive"))
    )
    (net (code "240") (name "unconnected-(CN500-Pad256)") (class "Default")
      (node (ref "CN500") (pin "256") (pinfunction "256_256") (pintype "passive"))
    )
    (net (code "241") (name "unconnected-(CN500-Pad257)") (class "Default")
      (node (ref "CN500") (pin "257") (pinfunction "257_257") (pintype "passive"))
    )
    (net (code "242") (name "unconnected-(CN500-Pad258)") (class "Default")
      (node (ref "CN500") (pin "258") (pinfunction "258_258") (pintype "passive"))
    )
    (net (code "243") (name "unconnected-(CN500-Pad259)") (class "Default")
      (node (ref "CN500") (pin "259") (pinfunction "259_259") (pintype "passive"))
    )
    (net (code "244") (name "unconnected-(CN500-Pad260)") (class "Default")
      (node (ref "CN500") (pin "260") (pinfunction "260_260") (pintype "passive"))
    )
  )
)
